# SPI.net
KiCad netlist of a schematic drawn in Altium Designer
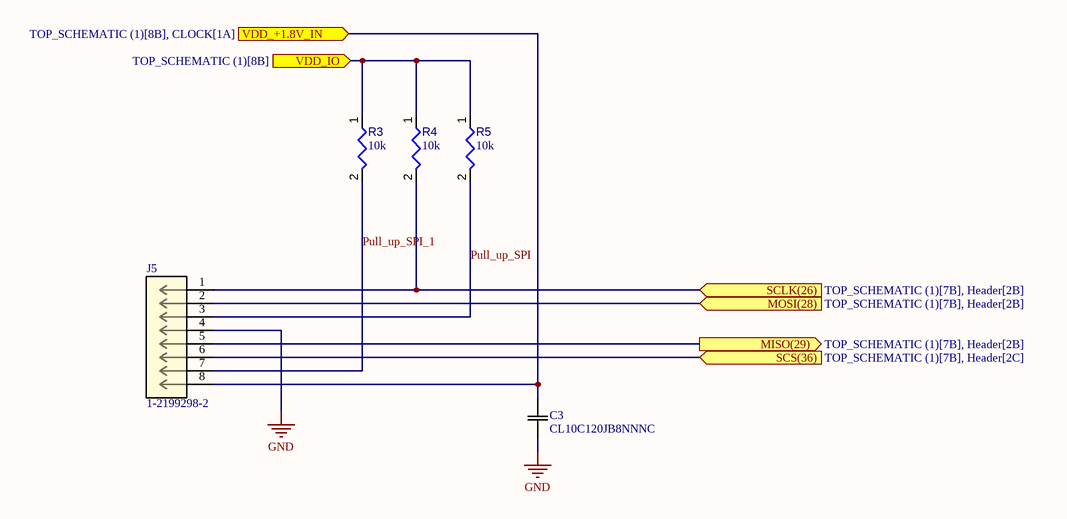
[diagram p0: SPI.SchDoc]

(export (version "E")
  (design (tool "Eeschema 10.0.6"))
  (components
    (comp (ref "C3")
      (value "CL10C120JB8NNNC")
      (footprint "CAP_CL10_SAM")
      (description "No Description Available")
      (fields (field (name "COPYRIGHT") "Copyright (C) 2026 Ultra Librarian. All rights reserved."))
      (libsource (lib "Cap_0603") (part "CL10C120JB8NNNC"))
    )
    (comp (ref "J5")
      (value "1-2199298-2")
      (footprint "CONN8_1-2199298-2_TEC")
      (description "8P,DIP SKT,300 CL,LDR,PB FREE")
      (fields (field (name "COPYRIGHT") "Copyright (C) 2026 Ultra Librarian. All rights reserved."))
      (libsource (lib "1-2199298-2") (part "1-2199298-2"))
    )
    (comp (ref "R3")
      (value "10k")
      (footprint "RESC2013X50X35ML15T15")
      (description "Chip Resistor, 10 KOhm, +/- 1%, 125 mW, -55 to 155 degC, 0805 (2012 Metric)")
      (fields (field (name "TOLERANCE") "1%") (field (name "POWER") "125mW"))
      (libsource (lib "Wilbert Román") (part "RES-2"))
    )
    (comp (ref "R4")
      (value "10k")
      (footprint "RESC2013X50X35ML15T15")
      (description "Chip Resistor, 10 KOhm, +/- 1%, 125 mW, -55 to 155 degC, 0805 (2012 Metric)")
      (fields (field (name "TOLERANCE") "1%") (field (name "POWER") "125mW"))
      (libsource (lib "Wilbert Román") (part "RES-2"))
    )
    (comp (ref "R5")
      (value "10k")
      (footprint "RESC2013X50X35ML15T15")
      (description "Chip Resistor, 10 KOhm, +/- 1%, 125 mW, -55 to 155 degC, 0805 (2012 Metric)")
      (fields (field (name "TOLERANCE") "1%") (field (name "POWER") "125mW"))
      (libsource (lib "Wilbert Román") (part "RES-2"))
    )
  )
  (nets
    (net (code "1") (name "/MISO(29)") (class "Default")
      (node (ref "J5") (pin "5") (pinfunction "5_5") (pintype "passive"))
    )
    (net (code "2") (name "/MOSI(28)") (class "Default")
      (node (ref "J5") (pin "2") (pinfunction "2_2") (pintype "passive"))
    )
    (net (code "3") (name "/Pull_up_SPI") (class "Default")
      (node (ref "J5") (pin "3") (pinfunction "3_3") (pintype "passive"))
      (node (ref "R5") (pin "2") (pinfunction "2_2") (pintype "passive"))
    )
    (net (code "4") (name "/Pull_up_SPI_1") (class "Default")
      (node (ref "J5") (pin "7") (pinfunction "7_7") (pintype "passive"))
      (node (ref "R3") (pin "2") (pinfunction "2_2") (pintype "passive"))
    )
    (net (code "5") (name "/SCLK(26)") (class "Default")
      (node (ref "J5") (pin "1") (pinfunction "1_1") (pintype "passive"))
      (node (ref "R4") (pin "2") (pinfunction "2_2") (pintype "passive"))
    )
    (net (code "6") (name "/SCS(36)") (class "Default")
      (node (ref "J5") (pin "6") (pinfunction "6_6") (pintype "passive"))
    )
    (net (code "7") (name "/VDD_+1.8V_IN") (class "Default")
      (node (ref "C3") (pin "2") (pinfunction "2_2") (pintype "passive"))
      (node (ref "J5") (pin "8") (pinfunction "8_8") (pintype "passive"))
    )
    (net (code "8") (name "/VDD_IO") (class "Default")
      (node (ref "R3") (pin "1") (pinfunction "1_1") (pintype "passive"))
      (node (ref "R4") (pin "1") (pinfunction "1_1") (pintype "passive"))
      (node (ref "R5") (pin "1") (pinfunction "1_1") (pintype "passive"))
    )
    (net (code "9") (name "GND") (class "Default")
      (node (ref "C3") (pin "1") (pinfunction "1_1") (pintype "passive"))
      (node (ref "J5") (pin "4") (pinfunction "4_4") (pintype "passive"))
    )
  )
)
